# ESC_PCB.net
KiCad netlist of a schematic drawn in Altium Designer
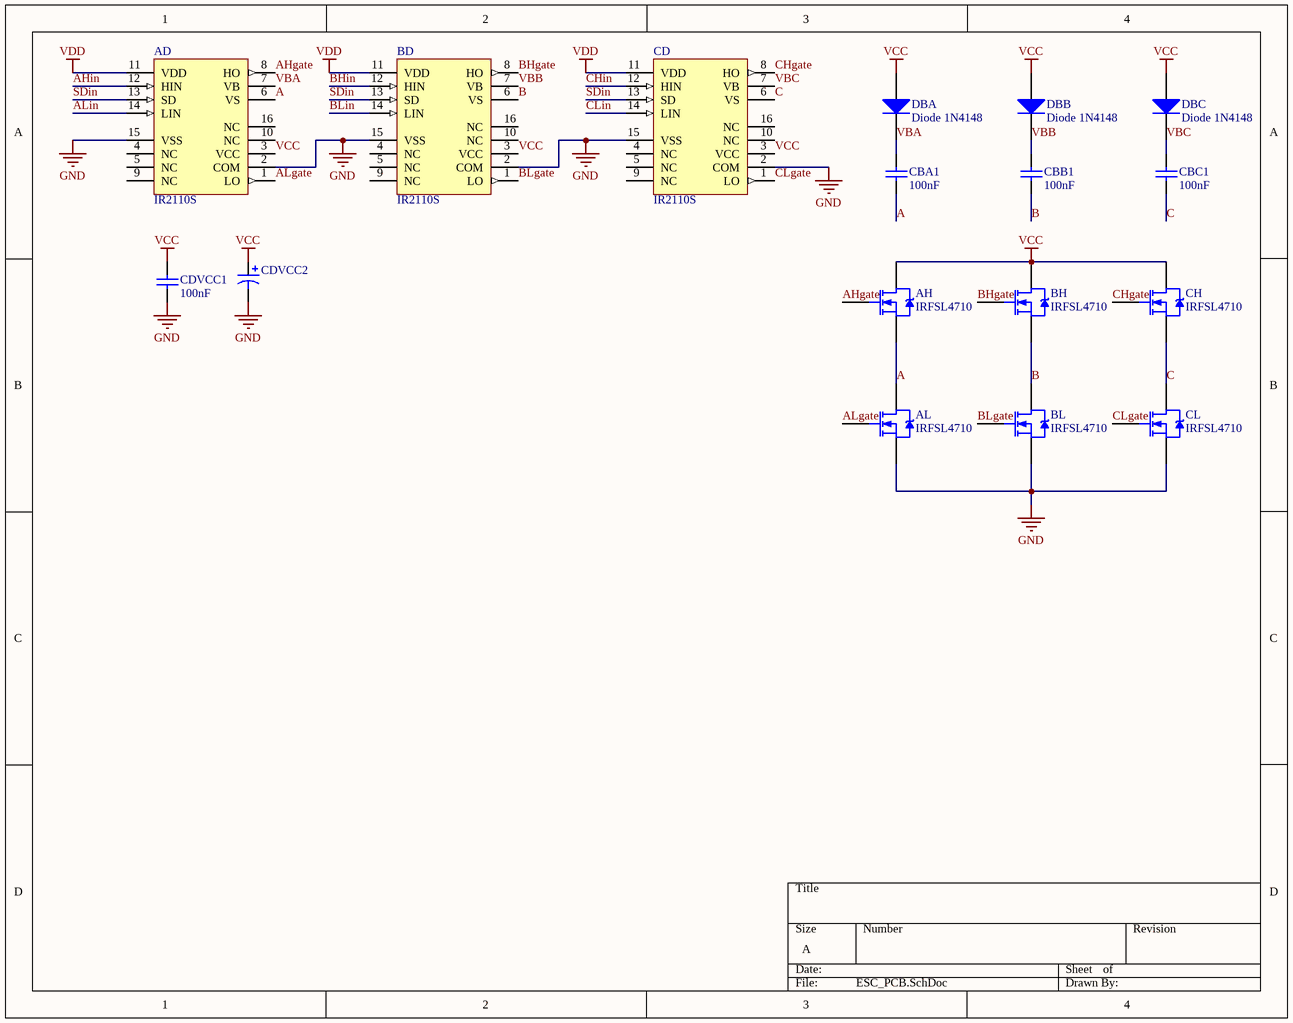
[diagram p0: ESC_PCB.SchDoc]

(export (version "E")
  (design (tool "Eeschema 10.0.6"))
  (components
    (comp (ref "AD")
      (value "IR2110S")
      (footprint "SOIC16_N")
      (description "High and Low Side Driver")
      (fields (field (name "PUBLISHER") "Altium Limited"))
      (libsource (lib "IR Interface Bridge Driver") (part "IR2110S"))
    )
    (comp (ref "AH")
      (value "IRFSL4710")
      (footprint "TO-262")
      (description "HEXFET Power MOSFET")
      (fields (field (name "PUBLISHER") "Altium Limited"))
      (libsource (lib "IR Discrete MOSFET - Power") (part "IRFSL4710"))
    )
    (comp (ref "AL")
      (value "IRFSL4710")
      (footprint "TO-262")
      (description "HEXFET Power MOSFET")
      (fields (field (name "PUBLISHER") "Altium Limited"))
      (libsource (lib "IR Discrete MOSFET - Power") (part "IRFSL4710"))
    )
    (comp (ref "BD")
      (value "IR2110S")
      (footprint "SOIC16_N")
      (description "High and Low Side Driver")
      (fields (field (name "PUBLISHER") "Altium Limited"))
      (libsource (lib "IR Interface Bridge Driver") (part "IR2110S"))
    )
    (comp (ref "BH")
      (value "IRFSL4710")
      (footprint "TO-262")
      (description "HEXFET Power MOSFET")
      (fields (field (name "PUBLISHER") "Altium Limited"))
      (libsource (lib "IR Discrete MOSFET - Power") (part "IRFSL4710"))
    )
    (comp (ref "BL")
      (value "IRFSL4710")
      (footprint "TO-262")
      (description "HEXFET Power MOSFET")
      (fields (field (name "PUBLISHER") "Altium Limited"))
      (libsource (lib "IR Discrete MOSFET - Power") (part "IRFSL4710"))
    )
    (comp (ref "CBA1")
      (value "100nF")
      (footprint "VP31-2.5")
      (description "Dipped Radial Multilayer Ceramic Capacitor X7R: 10nF")
      (fields (field (name "PUBLISHER") "Altium Limited"))
      (libsource (lib "Vishay Vitramon Ceramic Dipped Capacitor") (part "VP31BY103"))
    )
    (comp (ref "CBB1")
      (value "100nF")
      (footprint "VP31-2.5")
      (description "Dipped Radial Multilayer Ceramic Capacitor X7R: 10nF")
      (fields (field (name "PUBLISHER") "Altium Limited"))
      (libsource (lib "Vishay Vitramon Ceramic Dipped Capacitor") (part "VP31BY103"))
    )
    (comp (ref "CBC1")
      (value "100nF")
      (footprint "VP31-2.5")
      (description "Dipped Radial Multilayer Ceramic Capacitor X7R: 10nF")
      (fields (field (name "PUBLISHER") "Altium Limited"))
      (libsource (lib "Vishay Vitramon Ceramic Dipped Capacitor") (part "VP31BY103"))
    )
    (comp (ref "CD")
      (value "IR2110S")
      (footprint "SOIC16_N")
      (description "High and Low Side Driver")
      (fields (field (name "PUBLISHER") "Altium Limited"))
      (libsource (lib "IR Interface Bridge Driver") (part "IR2110S"))
    )
    (comp (ref "CDVCC1")
      (value "100nF")
      (footprint "VP31-2.5")
      (description "Dipped Radial Multilayer Ceramic Capacitor X7R: 10nF")
      (fields (field (name "PUBLISHER") "Altium Limited"))
      (libsource (lib "Vishay Vitramon Ceramic Dipped Capacitor") (part "VP31BY103"))
    )
    (comp (ref "CDVCC2")
      (value "EKF00MP133J00")
      (footprint "CAPPR2-5X5")
      (description "Aluminum Electrolytic Capacitor, Radial Style with Long Leads: 3.3uF, 63V")
      (fields (field (name "PUBLISHER") "Altium Limited"))
      (libsource (lib "Vishay Roederstein Electrolytic Radial-Lead Capacitor") (part "EKF00MP133J00"))
    )
    (comp (ref "CH")
      (value "IRFSL4710")
      (footprint "TO-262")
      (description "HEXFET Power MOSFET")
      (fields (field (name "PUBLISHER") "Altium Limited"))
      (libsource (lib "IR Discrete MOSFET - Power") (part "IRFSL4710"))
    )
    (comp (ref "CL")
      (value "IRFSL4710")
      (footprint "TO-262")
      (description "HEXFET Power MOSFET")
      (fields (field (name "PUBLISHER") "Altium Limited"))
      (libsource (lib "IR Discrete MOSFET - Power") (part "IRFSL4710"))
    )
    (comp (ref "DBA")
      (value "Diode 1N4148")
      (footprint "DO-35")
      (description "High Conductance Fast Diode")
      (fields (field (name "PUBLISHER") "Altium Limited"))
      (libsource (lib "Miscellaneous Devices") (part "Diode 1N4148"))
    )
    (comp (ref "DBB")
      (value "Diode 1N4148")
      (footprint "DO-35")
      (description "High Conductance Fast Diode")
      (fields (field (name "PUBLISHER") "Altium Limited"))
      (libsource (lib "Miscellaneous Devices") (part "Diode 1N4148"))
    )
    (comp (ref "DBC")
      (value "Diode 1N4148")
      (footprint "DO-35")
      (description "High Conductance Fast Diode")
      (fields (field (name "PUBLISHER") "Altium Limited"))
      (libsource (lib "Miscellaneous Devices") (part "Diode 1N4148"))
    )
  )
  (nets
    (net (code "1") (name "/A") (class "Default")
      (node (ref "AD") (pin "6") (pinfunction "VS_6") (pintype "power_in"))
      (node (ref "AH") (pin "3") (pinfunction "S_3") (pintype "passive"))
      (node (ref "AL") (pin "2") (pinfunction "D_2") (pintype "passive"))
      (node (ref "CBA1") (pin "1") (pinfunction "1_1") (pintype "passive"))
    )
    (net (code "2") (name "/AHgate") (class "Default")
      (node (ref "AD") (pin "8") (pinfunction "HO_8") (pintype "output"))
      (node (ref "AH") (pin "1") (pinfunction "G_1") (pintype "passive"))
    )
    (net (code "3") (name "/AHin") (class "Default")
      (node (ref "AD") (pin "12") (pinfunction "HIN_12") (pintype "input"))
    )
    (net (code "4") (name "/ALgate") (class "Default")
      (node (ref "AD") (pin "1") (pinfunction "LO_1") (pintype "output"))
      (node (ref "AL") (pin "1") (pinfunction "G_1") (pintype "passive"))
    )
    (net (code "5") (name "/ALin") (class "Default")
      (node (ref "AD") (pin "14") (pinfunction "LIN_14") (pintype "input"))
    )
    (net (code "6") (name "/B") (class "Default")
      (node (ref "BD") (pin "6") (pinfunction "VS_6") (pintype "power_in"))
      (node (ref "BH") (pin "3") (pinfunction "S_3") (pintype "passive"))
      (node (ref "BL") (pin "2") (pinfunction "D_2") (pintype "passive"))
      (node (ref "CBB1") (pin "1") (pinfunction "1_1") (pintype "passive"))
    )
    (net (code "7") (name "/BHgate") (class "Default")
      (node (ref "BD") (pin "8") (pinfunction "HO_8") (pintype "output"))
      (node (ref "BH") (pin "1") (pinfunction "G_1") (pintype "passive"))
    )
    (net (code "8") (name "/BHin") (class "Default")
      (node (ref "BD") (pin "12") (pinfunction "HIN_12") (pintype "input"))
    )
    (net (code "9") (name "/BLgate") (class "Default")
      (node (ref "BD") (pin "1") (pinfunction "LO_1") (pintype "output"))
      (node (ref "BL") (pin "1") (pinfunction "G_1") (pintype "passive"))
    )
    (net (code "10") (name "/BLin") (class "Default")
      (node (ref "BD") (pin "14") (pinfunction "LIN_14") (pintype "input"))
    )
    (net (code "11") (name "/C") (class "Default")
      (node (ref "CBC1") (pin "1") (pinfunction "1_1") (pintype "passive"))
      (node (ref "CD") (pin "6") (pinfunction "VS_6") (pintype "power_in"))
      (node (ref "CH") (pin "3") (pinfunction "S_3") (pintype "passive"))
      (node (ref "CL") (pin "2") (pinfunction "D_2") (pintype "passive"))
    )
    (net (code "12") (name "/CHgate") (class "Default")
      (node (ref "CD") (pin "8") (pinfunction "HO_8") (pintype "output"))
      (node (ref "CH") (pin "1") (pinfunction "G_1") (pintype "passive"))
    )
    (net (code "13") (name "/CHin") (class "Default")
      (node (ref "CD") (pin "12") (pinfunction "HIN_12") (pintype "input"))
    )
    (net (code "14") (name "/CLgate") (class "Default")
      (node (ref "CD") (pin "1") (pinfunction "LO_1") (pintype "output"))
      (node (ref "CL") (pin "1") (pinfunction "G_1") (pintype "passive"))
    )
    (net (code "15") (name "/CLin") (class "Default")
      (node (ref "CD") (pin "14") (pinfunction "LIN_14") (pintype "input"))
    )
    (net (code "16") (name "/SDin") (class "Default")
      (node (ref "AD") (pin "13") (pinfunction "SD_13") (pintype "input"))
      (node (ref "BD") (pin "13") (pinfunction "SD_13") (pintype "input"))
      (node (ref "CD") (pin "13") (pinfunction "SD_13") (pintype "input"))
    )
    (net (code "17") (name "/VBA") (class "Default")
      (node (ref "AD") (pin "7") (pinfunction "VB_7") (pintype "power_in"))
      (node (ref "CBA1") (pin "2") (pinfunction "2_2") (pintype "passive"))
      (node (ref "DBA") (pin "2") (pinfunction "K_2") (pintype "passive"))
    )
    (net (code "18") (name "/VBB") (class "Default")
      (node (ref "BD") (pin "7") (pinfunction "VB_7") (pintype "power_in"))
      (node (ref "CBB1") (pin "2") (pinfunction "2_2") (pintype "passive"))
      (node (ref "DBB") (pin "2") (pinfunction "K_2") (pintype "passive"))
    )
    (net (code "19") (name "/VBC") (class "Default")
      (node (ref "CBC1") (pin "2") (pinfunction "2_2") (pintype "passive"))
      (node (ref "CD") (pin "7") (pinfunction "VB_7") (pintype "power_in"))
      (node (ref "DBC") (pin "2") (pinfunction "K_2") (pintype "passive"))
    )
    (net (code "20") (name "GND") (class "Default")
      (node (ref "AD") (pin "15") (pinfunction "VSS_15") (pintype "power_in"))
      (node (ref "AD") (pin "2") (pinfunction "COM_2") (pintype "power_in"))
      (node (ref "AL") (pin "3") (pinfunction "S_3") (pintype "passive"))
      (node (ref "BD") (pin "15") (pinfunction "VSS_15") (pintype "power_in"))
      (node (ref "BD") (pin "2") (pinfunction "COM_2") (pintype "power_in"))
      (node (ref "BL") (pin "3") (pinfunction "S_3") (pintype "passive"))
      (node (ref "CD") (pin "15") (pinfunction "VSS_15") (pintype "power_in"))
      (node (ref "CD") (pin "2") (pinfunction "COM_2") (pintype "power_in"))
      (node (ref "CDVCC1") (pin "1") (pinfunction "1_1") (pintype "passive"))
      (node (ref "CDVCC2") (pin "2") (pinfunction "2_2") (pintype "passive"))
      (node (ref "CL") (pin "3") (pinfunction "S_3") (pintype "passive"))
    )
    (net (code "21") (name "VCC") (class "Default")
      (node (ref "AD") (pin "3") (pinfunction "VCC_3") (pintype "power_in"))
      (node (ref "AH") (pin "2") (pinfunction "D_2") (pintype "passive"))
      (node (ref "BD") (pin "3") (pinfunction "VCC_3") (pintype "power_in"))
      (node (ref "BH") (pin "2") (pinfunction "D_2") (pintype "passive"))
      (node (ref "CD") (pin "3") (pinfunction "VCC_3") (pintype "power_in"))
      (node (ref "CDVCC1") (pin "2") (pinfunction "2_2") (pintype "passive"))
      (node (ref "CDVCC2") (pin "1") (pinfunction "1_1") (pintype "passive"))
      (node (ref "CH") (pin "2") (pinfunction "D_2") (pintype "passive"))
      (node (ref "DBA") (pin "1") (pinfunction "A_1") (pintype "passive"))
      (node (ref "DBB") (pin "1") (pinfunction "A_1") (pintype "passive"))
      (node (ref "DBC") (pin "1") (pinfunction "A_1") (pintype "passive"))
    )
    (net (code "22") (name "VDD") (class "Default")
      (node (ref "AD") (pin "11") (pinfunction "VDD_11") (pintype "power_in"))
      (node (ref "BD") (pin "11") (pinfunction "VDD_11") (pintype "power_in"))
      (node (ref "CD") (pin "11") (pinfunction "VDD_11") (pintype "power_in"))
    )
    (net (code "23") (name "unconnected-(AD-NC-Pad4)") (class "Default")
      (node (ref "AD") (pin "4") (pinfunction "NC_4") (pintype "passive"))
    )
    (net (code "24") (name "unconnected-(AD-NC-Pad5)") (class "Default")
      (node (ref "AD") (pin "5") (pinfunction "NC_5") (pintype "passive"))
    )
    (net (code "25") (name "unconnected-(AD-NC-Pad9)") (class "Default")
      (node (ref "AD") (pin "9") (pinfunction "NC_9") (pintype "passive"))
    )
    (net (code "26") (name "unconnected-(AD-NC-Pad10)") (class "Default")
      (node (ref "AD") (pin "10") (pinfunction "NC_10") (pintype "passive"))
    )
    (net (code "27") (name "unconnected-(AD-NC-Pad16)") (class "Default")
      (node (ref "AD") (pin "16") (pinfunction "NC_16") (pintype "passive"))
    )
    (net (code "28") (name "unconnected-(BD-NC-Pad4)") (class "Default")
      (node (ref "BD") (pin "4") (pinfunction "NC_4") (pintype "passive"))
    )
    (net (code "29") (name "unconnected-(BD-NC-Pad5)") (class "Default")
      (node (ref "BD") (pin "5") (pinfunction "NC_5") (pintype "passive"))
    )
    (net (code "30") (name "unconnected-(BD-NC-Pad9)") (class "Default")
      (node (ref "BD") (pin "9") (pinfunction "NC_9") (pintype "passive"))
    )
    (net (code "31") (name "unconnected-(BD-NC-Pad10)") (class "Default")
      (node (ref "BD") (pin "10") (pinfunction "NC_10") (pintype "passive"))
    )
    (net (code "32") (name "unconnected-(BD-NC-Pad16)") (class "Default")
      (node (ref "BD") (pin "16") (pinfunction "NC_16") (pintype "passive"))
    )
    (net (code "33") (name "unconnected-(CD-NC-Pad4)") (class "Default")
      (node (ref "CD") (pin "4") (pinfunction "NC_4") (pintype "passive"))
    )
    (net (code "34") (name "unconnected-(CD-NC-Pad5)") (class "Default")
      (node (ref "CD") (pin "5") (pinfunction "NC_5") (pintype "passive"))
    )
    (net (code "35") (name "unconnected-(CD-NC-Pad9)") (class "Default")
      (node (ref "CD") (pin "9") (pinfunction "NC_9") (pintype "passive"))
    )
    (net (code "36") (name "unconnected-(CD-NC-Pad10)") (class "Default")
      (node (ref "CD") (pin "10") (pinfunction "NC_10") (pintype "passive"))
    )
    (net (code "37") (name "unconnected-(CD-NC-Pad16)") (class "Default")
      (node (ref "CD") (pin "16") (pinfunction "NC_16") (pintype "passive"))
    )
  )
)
